# SP_Inverter_SW.net
KiCad netlist of a schematic drawn in EAGLE
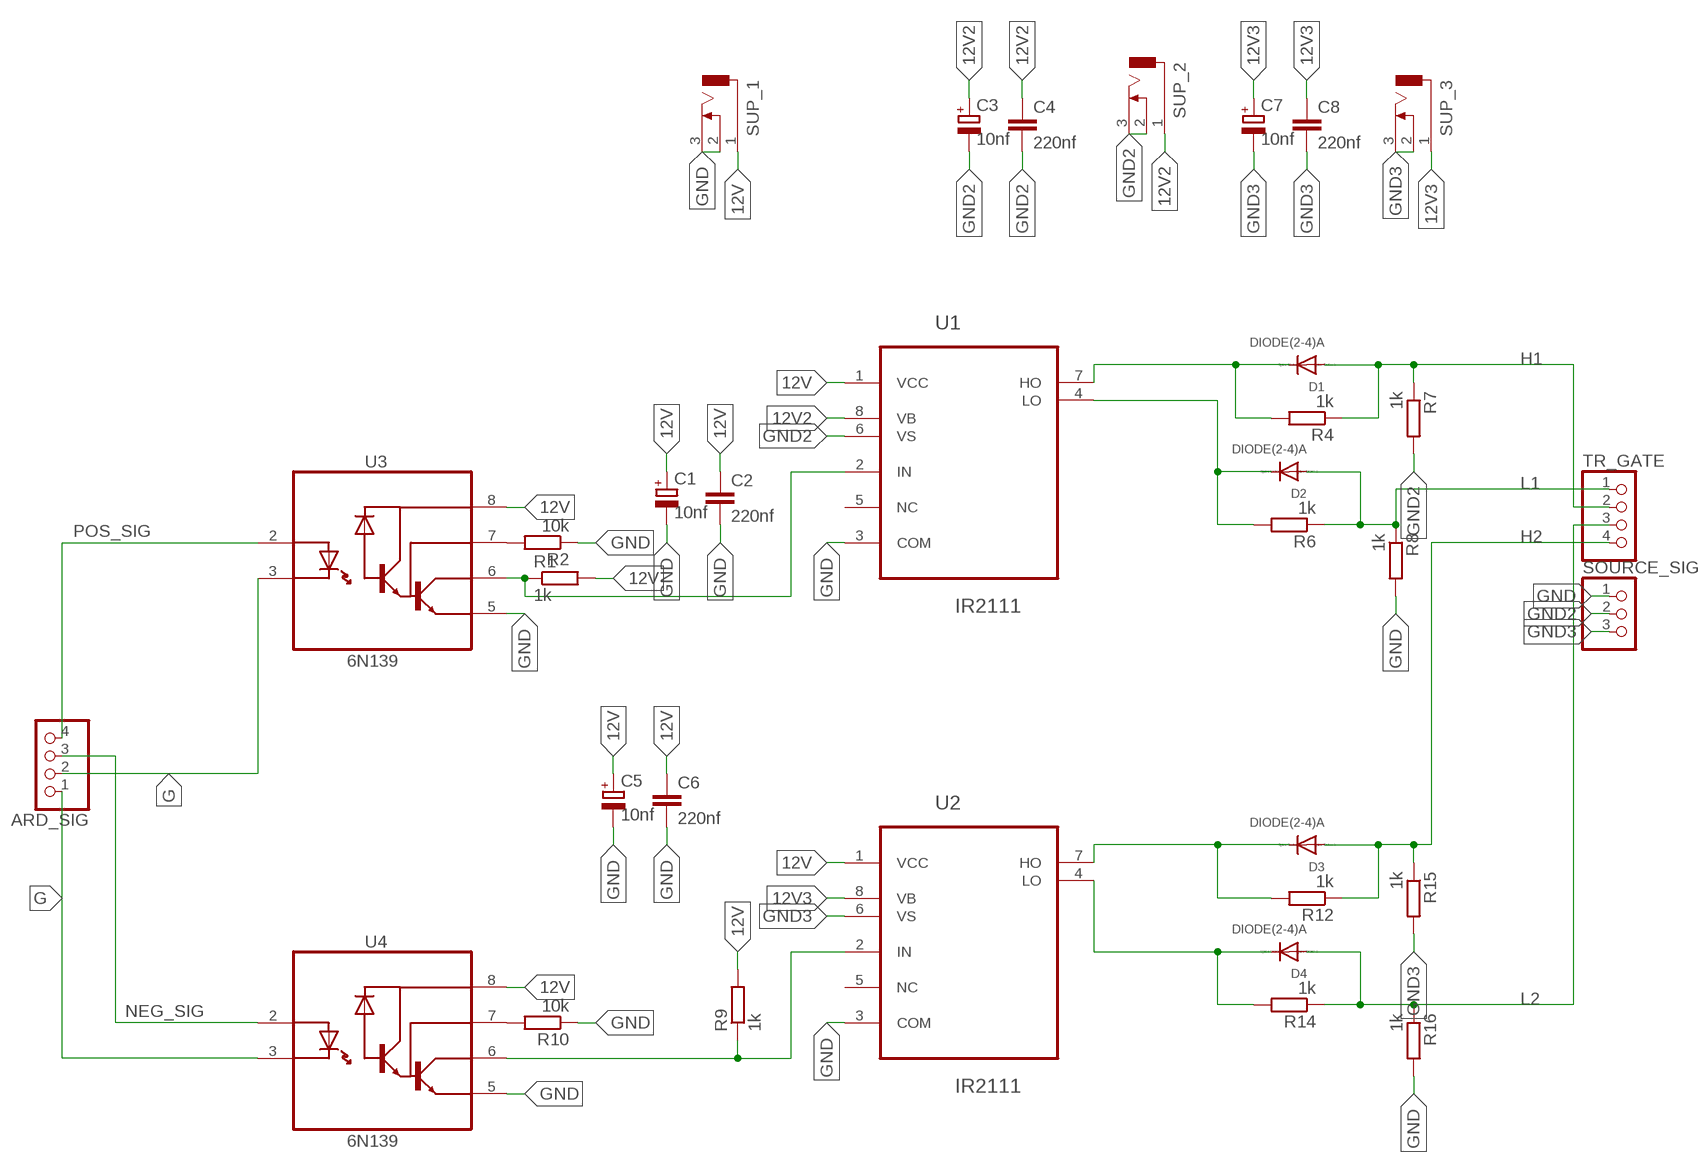
[diagram p0: schematic, sheet 1]

(export (version "E")
  (design (tool "Eeschema 10.0.6"))
  (components
    (comp (ref "ARD_SIG")
      (value "PINHD-1X4")
      (footprint "eagle-import:1X04")
      (libsource (lib "eagle-import") (part "PINHD-1X4"))
    )
    (comp (ref "C1")
      (value "10nf")
      (footprint "eagle-import:E3,5-8")
      (libsource (lib "eagle-import") (part "CAP_POL"))
    )
    (comp (ref "C2")
      (value "220nf")
      (footprint "eagle-import:C025-025X050")
      (libsource (lib "eagle-import") (part "CAPACITOR"))
    )
    (comp (ref "C3")
      (value "10nf")
      (footprint "eagle-import:E3,5-8")
      (libsource (lib "eagle-import") (part "CAP_POL"))
    )
    (comp (ref "C4")
      (value "220nf")
      (footprint "eagle-import:C025-025X050")
      (libsource (lib "eagle-import") (part "CAPACITOR"))
    )
    (comp (ref "C5")
      (value "10nf")
      (footprint "eagle-import:E3,5-8")
      (libsource (lib "eagle-import") (part "CAP_POL"))
    )
    (comp (ref "C6")
      (value "220nf")
      (footprint "eagle-import:C025-025X050")
      (libsource (lib "eagle-import") (part "CAPACITOR"))
    )
    (comp (ref "C7")
      (value "10nf")
      (footprint "eagle-import:E3,5-8")
      (libsource (lib "eagle-import") (part "CAP_POL"))
    )
    (comp (ref "C8")
      (value "220nf")
      (footprint "eagle-import:C025-025X050")
      (libsource (lib "eagle-import") (part "CAPACITOR"))
    )
    (comp (ref "D1")
      (value "DIODE(2-4)A")
      (footprint "eagle-import:DO35-10")
      (libsource (lib "eagle-import") (part "DIODE(2-4)A"))
    )
    (comp (ref "D2")
      (value "DIODE(2-4)A")
      (footprint "eagle-import:DO35-10")
      (libsource (lib "eagle-import") (part "DIODE(2-4)A"))
    )
    (comp (ref "D3")
      (value "DIODE(2-4)A")
      (footprint "eagle-import:DO35-10")
      (libsource (lib "eagle-import") (part "DIODE(2-4)A"))
    )
    (comp (ref "D4")
      (value "DIODE(2-4)A")
      (footprint "eagle-import:DO35-10")
      (libsource (lib "eagle-import") (part "DIODE(2-4)A"))
    )
    (comp (ref "R1")
      (value "1k")
      (footprint "eagle-import:0204_7")
      (libsource (lib "eagle-import") (part "R-EU_0204/7"))
    )
    (comp (ref "R2")
      (value "10k")
      (footprint "eagle-import:0204_7")
      (libsource (lib "eagle-import") (part "R-EU_0204/7"))
    )
    (comp (ref "R4")
      (value "1k")
      (footprint "eagle-import:0204_7")
      (libsource (lib "eagle-import") (part "R-EU_0204/7"))
    )
    (comp (ref "R6")
      (value "1k")
      (footprint "eagle-import:0204_7")
      (libsource (lib "eagle-import") (part "R-EU_0204/7"))
    )
    (comp (ref "R7")
      (value "1k")
      (footprint "eagle-import:0204_7")
      (libsource (lib "eagle-import") (part "R-EU_0204/7"))
    )
    (comp (ref "R8")
      (value "1k")
      (footprint "eagle-import:0204_7")
      (libsource (lib "eagle-import") (part "R-EU_0204/7"))
    )
    (comp (ref "R9")
      (value "1k")
      (footprint "eagle-import:0204_7")
      (libsource (lib "eagle-import") (part "R-EU_0204/7"))
    )
    (comp (ref "R10")
      (value "10k")
      (footprint "eagle-import:0204_7")
      (libsource (lib "eagle-import") (part "R-EU_0204/7"))
    )
    (comp (ref "R12")
      (value "1k")
      (footprint "eagle-import:0204_7")
      (libsource (lib "eagle-import") (part "R-EU_0204/7"))
    )
    (comp (ref "R14")
      (value "1k")
      (footprint "eagle-import:0204_7")
      (libsource (lib "eagle-import") (part "R-EU_0204/7"))
    )
    (comp (ref "R15")
      (value "1k")
      (footprint "eagle-import:0204_7")
      (libsource (lib "eagle-import") (part "R-EU_0204/7"))
    )
    (comp (ref "R16")
      (value "1k")
      (footprint "eagle-import:0204_7")
      (libsource (lib "eagle-import") (part "R-EU_0204/7"))
    )
    (comp (ref "SOURCE_SIG")
      (value "source_Sig")
      (footprint "eagle-import:1X03")
      (libsource (lib "eagle-import") (part "PINHD-1X3"))
    )
    (comp (ref "SUP_1")
      (value "CON_JACK")
      (footprint "eagle-import:DCJ0303")
      (libsource (lib "eagle-import") (part "CON_JACK"))
    )
    (comp (ref "SUP_2")
      (value "CON_JACK")
      (footprint "eagle-import:DCJ0303")
      (libsource (lib "eagle-import") (part "CON_JACK"))
    )
    (comp (ref "SUP_3")
      (value "CON_JACK")
      (footprint "eagle-import:DCJ0303")
      (libsource (lib "eagle-import") (part "CON_JACK"))
    )
    (comp (ref "TR_GATE")
      (value "PINHD-1X4")
      (footprint "eagle-import:1X04")
      (libsource (lib "eagle-import") (part "PINHD-1X4"))
    )
    (comp (ref "U1")
      (value "IR2111")
      (footprint "eagle-import:DIP254P762X533-8")
      (fields (field (name "MF") "Infineon"))
      (libsource (lib "eagle-import") (part "IR2111"))
    )
    (comp (ref "U2")
      (value "IR2111")
      (footprint "eagle-import:DIP254P762X533-8")
      (fields (field (name "MF") "Infineon"))
      (libsource (lib "eagle-import") (part "IR2111"))
    )
    (comp (ref "U3")
      (value "6N139")
      (footprint "eagle-import:DIP762W50P254L977H451Q8")
      (fields (field (name "MF") "Vishay Semiconductor"))
      (libsource (lib "eagle-import") (part "6N139"))
    )
    (comp (ref "U4")
      (value "6N139")
      (footprint "eagle-import:DIP762W50P254L977H451Q8")
      (fields (field (name "MF") "Vishay Semiconductor"))
      (libsource (lib "eagle-import") (part "6N139"))
    )
  )
  (nets
    (net (code "1") (name "/H1") (class "Default")
      (node (ref "D1") (pin "A") (pinfunction "A_A") (pintype "passive"))
      (node (ref "R4") (pin "1") (pinfunction "1_1") (pintype "passive"))
      (node (ref "R7") (pin "1") (pinfunction "1_1") (pintype "passive"))
      (node (ref "TR_GATE") (pin "2") (pinfunction "2_2") (pintype "passive"))
    )
    (net (code "2") (name "/H2") (class "Default")
      (node (ref "D3") (pin "A") (pinfunction "A_A") (pintype "passive"))
      (node (ref "R12") (pin "1") (pinfunction "1_1") (pintype "passive"))
      (node (ref "R15") (pin "1") (pinfunction "1_1") (pintype "passive"))
      (node (ref "TR_GATE") (pin "4") (pinfunction "4_4") (pintype "passive"))
    )
    (net (code "3") (name "/L1") (class "Default")
      (node (ref "D2") (pin "A") (pinfunction "A_A") (pintype "passive"))
      (node (ref "R6") (pin "1") (pinfunction "1_1") (pintype "passive"))
      (node (ref "R8") (pin "1") (pinfunction "1_1") (pintype "passive"))
      (node (ref "TR_GATE") (pin "1") (pinfunction "1_1") (pintype "passive"))
    )
    (net (code "4") (name "/L2") (class "Default")
      (node (ref "D4") (pin "A") (pinfunction "A_A") (pintype "passive"))
      (node (ref "R14") (pin "1") (pinfunction "1_1") (pintype "passive"))
      (node (ref "R16") (pin "1") (pinfunction "1_1") (pintype "passive"))
      (node (ref "TR_GATE") (pin "3") (pinfunction "3_3") (pintype "passive"))
    )
    (net (code "5") (name "/NEG_SIG") (class "Default")
      (node (ref "ARD_SIG") (pin "3") (pinfunction "3_3") (pintype "passive"))
      (node (ref "U4") (pin "2") (pinfunction "A_2") (pintype "passive"))
    )
    (net (code "6") (name "/POS_SIG") (class "Default")
      (node (ref "ARD_SIG") (pin "4") (pinfunction "4_4") (pintype "passive"))
      (node (ref "U3") (pin "2") (pinfunction "A_2") (pintype "passive"))
    )
    (net (code "7") (name "12V") (class "Default")
      (node (ref "C1") (pin "+") (pinfunction "+_+") (pintype "passive"))
      (node (ref "C2") (pin "1") (pinfunction "1_1") (pintype "passive"))
      (node (ref "C5") (pin "+") (pinfunction "+_+") (pintype "passive"))
      (node (ref "C6") (pin "1") (pinfunction "1_1") (pintype "passive"))
      (node (ref "R1") (pin "2") (pinfunction "2_2") (pintype "passive"))
      (node (ref "R9") (pin "2") (pinfunction "2_2") (pintype "passive"))
      (node (ref "SUP_1") (pin "1") (pinfunction "1_1") (pintype "passive"))
      (node (ref "U1") (pin "1") (pinfunction "VCC_1") (pintype "power_in"))
      (node (ref "U2") (pin "1") (pinfunction "VCC_1") (pintype "power_in"))
      (node (ref "U3") (pin "8") (pinfunction "VCC_8") (pintype "power_in"))
      (node (ref "U4") (pin "8") (pinfunction "VCC_8") (pintype "power_in"))
    )
    (net (code "8") (name "12V2") (class "Default")
      (node (ref "C3") (pin "+") (pinfunction "+_+") (pintype "passive"))
      (node (ref "C4") (pin "1") (pinfunction "1_1") (pintype "passive"))
      (node (ref "SUP_2") (pin "1") (pinfunction "1_1") (pintype "passive"))
      (node (ref "U1") (pin "8") (pinfunction "VB_8") (pintype "power_in"))
    )
    (net (code "9") (name "12V3") (class "Default")
      (node (ref "C7") (pin "+") (pinfunction "+_+") (pintype "passive"))
      (node (ref "C8") (pin "1") (pinfunction "1_1") (pintype "passive"))
      (node (ref "SUP_3") (pin "1") (pinfunction "1_1") (pintype "passive"))
      (node (ref "U2") (pin "8") (pinfunction "VB_8") (pintype "power_in"))
    )
    (net (code "10") (name "G") (class "Default")
      (node (ref "ARD_SIG") (pin "1") (pinfunction "1_1") (pintype "passive"))
      (node (ref "ARD_SIG") (pin "2") (pinfunction "2_2") (pintype "passive"))
      (node (ref "U3") (pin "3") (pinfunction "C_3") (pintype "passive"))
      (node (ref "U4") (pin "3") (pinfunction "C_3") (pintype "passive"))
    )
    (net (code "11") (name "GND") (class "Default")
      (node (ref "C1") (pin "-") (pinfunction "-_-") (pintype "passive"))
      (node (ref "C2") (pin "2") (pinfunction "2_2") (pintype "passive"))
      (node (ref "C5") (pin "-") (pinfunction "-_-") (pintype "passive"))
      (node (ref "C6") (pin "2") (pinfunction "2_2") (pintype "passive"))
      (node (ref "R10") (pin "1") (pinfunction "1_1") (pintype "passive"))
      (node (ref "R16") (pin "2") (pinfunction "2_2") (pintype "passive"))
      (node (ref "R2") (pin "1") (pinfunction "1_1") (pintype "passive"))
      (node (ref "R8") (pin "2") (pinfunction "2_2") (pintype "passive"))
      (node (ref "SOURCE_SIG") (pin "1") (pinfunction "1_1") (pintype "passive"))
      (node (ref "SUP_1") (pin "2") (pinfunction "2_2") (pintype "passive"))
      (node (ref "SUP_1") (pin "3") (pinfunction "3_3") (pintype "passive"))
      (node (ref "U1") (pin "3") (pinfunction "COM_3") (pintype "passive"))
      (node (ref "U2") (pin "3") (pinfunction "COM_3") (pintype "passive"))
      (node (ref "U3") (pin "5") (pinfunction "GND_5") (pintype "power_in"))
      (node (ref "U4") (pin "5") (pinfunction "GND_5") (pintype "power_in"))
    )
    (net (code "12") (name "GND2") (class "Default")
      (node (ref "C3") (pin "-") (pinfunction "-_-") (pintype "passive"))
      (node (ref "C4") (pin "2") (pinfunction "2_2") (pintype "passive"))
      (node (ref "R7") (pin "2") (pinfunction "2_2") (pintype "passive"))
      (node (ref "SOURCE_SIG") (pin "2") (pinfunction "2_2") (pintype "passive"))
      (node (ref "SUP_2") (pin "2") (pinfunction "2_2") (pintype "passive"))
      (node (ref "SUP_2") (pin "3") (pinfunction "3_3") (pintype "passive"))
      (node (ref "U1") (pin "6") (pinfunction "VS_6") (pintype "power_in"))
    )
    (net (code "13") (name "GND3") (class "Default")
      (node (ref "C7") (pin "-") (pinfunction "-_-") (pintype "passive"))
      (node (ref "C8") (pin "2") (pinfunction "2_2") (pintype "passive"))
      (node (ref "R15") (pin "2") (pinfunction "2_2") (pintype "passive"))
      (node (ref "SOURCE_SIG") (pin "3") (pinfunction "3_3") (pintype "passive"))
      (node (ref "SUP_3") (pin "2") (pinfunction "2_2") (pintype "passive"))
      (node (ref "SUP_3") (pin "3") (pinfunction "3_3") (pintype "passive"))
      (node (ref "U2") (pin "6") (pinfunction "VS_6") (pintype "power_in"))
    )
    (net (code "14") (name "Net-(U1-HO)") (class "Default")
      (node (ref "D1") (pin "C") (pinfunction "C_C") (pintype "passive"))
      (node (ref "R4") (pin "2") (pinfunction "2_2") (pintype "passive"))
      (node (ref "U1") (pin "7") (pinfunction "HO_7") (pintype "output"))
    )
    (net (code "15") (name "Net-(U1-IN)") (class "Default")
      (node (ref "R1") (pin "1") (pinfunction "1_1") (pintype "passive"))
      (node (ref "U1") (pin "2") (pinfunction "IN_2") (pintype "input"))
      (node (ref "U3") (pin "6") (pinfunction "VO_6") (pintype "passive"))
    )
    (net (code "16") (name "Net-(U1-LO)") (class "Default")
      (node (ref "D2") (pin "C") (pinfunction "C_C") (pintype "passive"))
      (node (ref "R6") (pin "2") (pinfunction "2_2") (pintype "passive"))
      (node (ref "U1") (pin "4") (pinfunction "LO_4") (pintype "output"))
    )
    (net (code "17") (name "Net-(U2-HO)") (class "Default")
      (node (ref "D3") (pin "C") (pinfunction "C_C") (pintype "passive"))
      (node (ref "R12") (pin "2") (pinfunction "2_2") (pintype "passive"))
      (node (ref "U2") (pin "7") (pinfunction "HO_7") (pintype "output"))
    )
    (net (code "18") (name "Net-(U2-IN)") (class "Default")
      (node (ref "R9") (pin "1") (pinfunction "1_1") (pintype "passive"))
      (node (ref "U2") (pin "2") (pinfunction "IN_2") (pintype "input"))
      (node (ref "U4") (pin "6") (pinfunction "VO_6") (pintype "passive"))
    )
    (net (code "19") (name "Net-(U2-LO)") (class "Default")
      (node (ref "D4") (pin "C") (pinfunction "C_C") (pintype "passive"))
      (node (ref "R14") (pin "2") (pinfunction "2_2") (pintype "passive"))
      (node (ref "U2") (pin "4") (pinfunction "LO_4") (pintype "output"))
    )
    (net (code "20") (name "Net-(U3-VB)") (class "Default")
      (node (ref "R2") (pin "2") (pinfunction "2_2") (pintype "passive"))
      (node (ref "U3") (pin "7") (pinfunction "VB_7") (pintype "passive"))
    )
    (net (code "21") (name "Net-(U4-VB)") (class "Default")
      (node (ref "R10") (pin "2") (pinfunction "2_2") (pintype "passive"))
      (node (ref "U4") (pin "7") (pinfunction "VB_7") (pintype "passive"))
    )
    (net (code "22") (name "unconnected-(U1-NC-Pad5)") (class "Default")
      (node (ref "U1") (pin "5") (pinfunction "NC_5") (pintype "no_connect"))
    )
    (net (code "23") (name "unconnected-(U2-NC-Pad5)") (class "Default")
      (node (ref "U2") (pin "5") (pinfunction "NC_5") (pintype "no_connect"))
    )
  )
)
